# Triple_axis_digital_-_output_gyro_ITG-32.net
KiCad netlist of a schematic drawn in EAGLE
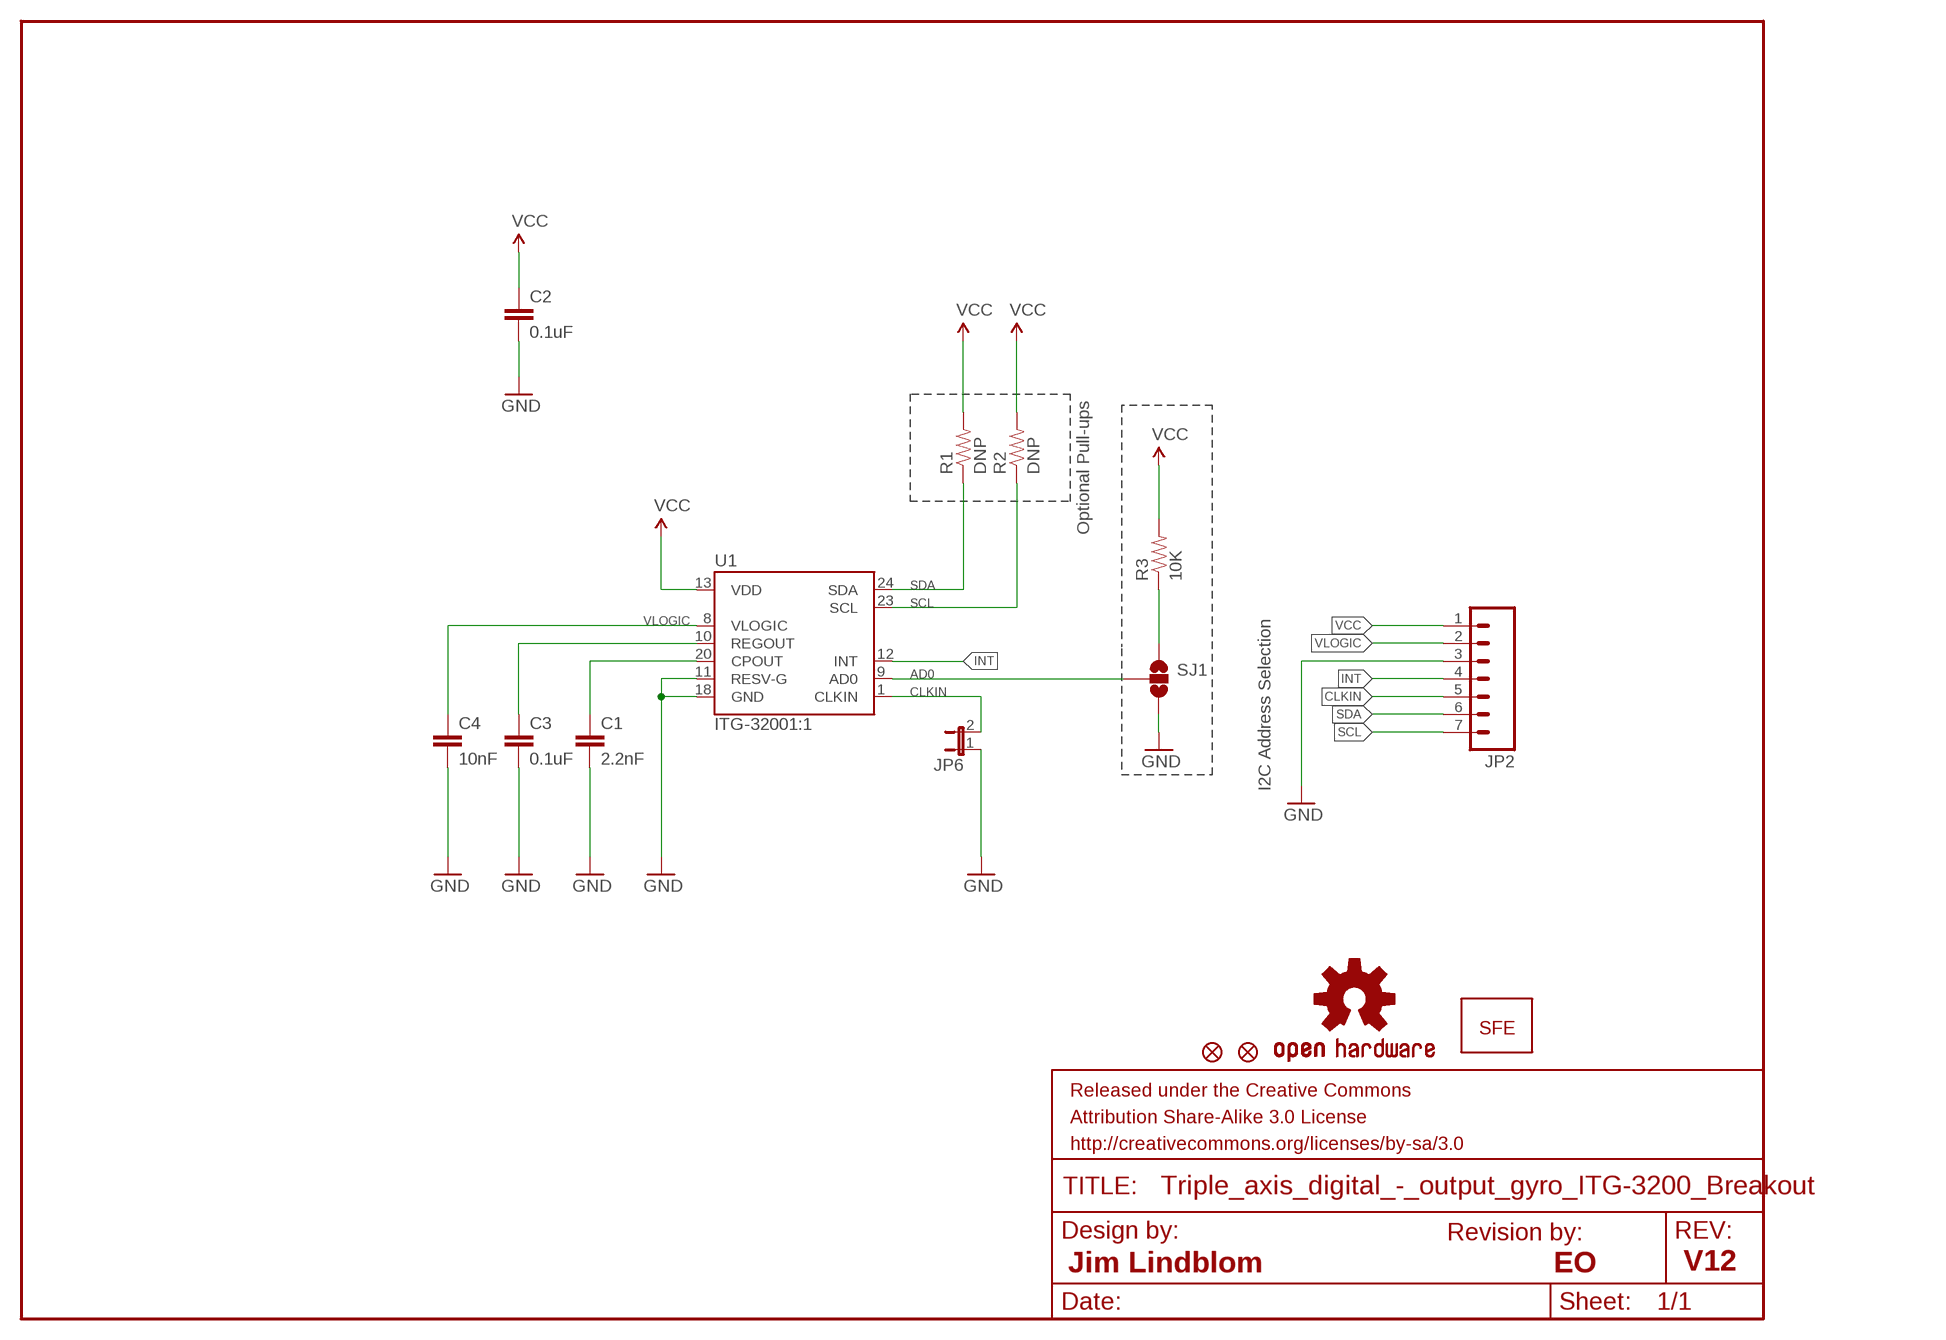
[diagram p0: schematic, sheet 1]

(export (version "E")
  (design (tool "Eeschema 10.0.6"))
  (components
    (comp (ref "C1")
      (value "2.2nF")
      (footprint "eagle-import:0603-CAP")
      (libsource (lib "eagle-import") (part "CAP0603-CAP"))
    )
    (comp (ref "C2")
      (value "0.1uF")
      (footprint "eagle-import:0603-CAP")
      (libsource (lib "eagle-import") (part "CAP0603-CAP"))
    )
    (comp (ref "C3")
      (value "0.1uF")
      (footprint "eagle-import:0603-CAP")
      (libsource (lib "eagle-import") (part "CAP0603-CAP"))
    )
    (comp (ref "C4")
      (value "10nF")
      (footprint "eagle-import:0603-CAP")
      (libsource (lib "eagle-import") (part "CAP0603-CAP"))
    )
    (comp (ref "FID1")
      (value "FIDUCIALUFIDUCIAL")
      (footprint "eagle-import:MICRO-FIDUCIAL")
      (libsource (lib "eagle-import") (part "FIDUCIALUFIDUCIAL"))
    )
    (comp (ref "FID2")
      (value "FIDUCIALUFIDUCIAL")
      (footprint "eagle-import:MICRO-FIDUCIAL")
      (libsource (lib "eagle-import") (part "FIDUCIALUFIDUCIAL"))
    )
    (comp (ref "FRAME1")
      (value "FRAME-LETTER")
      (footprint "eagle-import:CREATIVE_COMMONS")
      (libsource (lib "eagle-import") (part "FRAME-LETTER"))
    )
    (comp (ref "JP2")
      (value "M07")
      (footprint "eagle-import:1X07")
      (libsource (lib "eagle-import") (part "M07"))
    )
    (comp (ref "JP6")
      (value "JUMPER-2SMD-NO")
      (footprint "eagle-import:SJ_2S-NO")
      (libsource (lib "eagle-import") (part "JUMPER-2SMD-NO"))
    )
    (comp (ref "LOGO1")
      (value "OSHW-LOGOS")
      (footprint "eagle-import:OSHW-LOGO-S")
      (libsource (lib "eagle-import") (part "OSHW-LOGOS"))
    )
    (comp (ref "LOGO2")
      (value "LOGO-SFESK")
      (footprint "eagle-import:SFE-LOGO-FLAME")
      (libsource (lib "eagle-import") (part "LOGO-SFESK"))
    )
    (comp (ref "R1")
      (value "DNP")
      (footprint "eagle-import:0603-RES")
      (libsource (lib "eagle-import") (part "RESISTOR0603-RES"))
    )
    (comp (ref "R2")
      (value "DNP")
      (footprint "eagle-import:0603-RES")
      (libsource (lib "eagle-import") (part "RESISTOR0603-RES"))
    )
    (comp (ref "R3")
      (value "10K")
      (footprint "eagle-import:0603-RES")
      (libsource (lib "eagle-import") (part "10KOHM1/10W1%(0603)0603"))
    )
    (comp (ref "SJ1")
      (value "SOLDERJUMPER_2WAYPASTE1&2")
      (footprint "eagle-import:SJ_3_PASTE1&2")
      (libsource (lib "eagle-import") (part "SOLDERJUMPER_2WAYPASTE1&2"))
    )
    (comp (ref "U1")
      (value "ITG-32001:1")
      (footprint "eagle-import:QFN-24_ITG3200_1_1")
      (libsource (lib "eagle-import") (part "ITG-32001{colon}1"))
    )
  )
  (nets
    (net (code "1") (name "/AD0") (class "Default")
      (node (ref "SJ1") (pin "2") (pinfunction "2_2") (pintype "passive"))
      (node (ref "U1") (pin "9") (pinfunction "AD0_9") (pintype "bidirectional"))
    )
    (net (code "2") (name "CLKIN") (class "Default")
      (node (ref "JP2") (pin "5") (pinfunction "5_5") (pintype "passive"))
      (node (ref "JP6") (pin "2") (pinfunction "2_2") (pintype "passive"))
      (node (ref "U1") (pin "1") (pinfunction "CLKIN_1") (pintype "bidirectional"))
    )
    (net (code "3") (name "GND") (class "Default")
      (node (ref "C1") (pin "2") (pinfunction "2_2") (pintype "passive"))
      (node (ref "C2") (pin "2") (pinfunction "2_2") (pintype "passive"))
      (node (ref "C3") (pin "2") (pinfunction "2_2") (pintype "passive"))
      (node (ref "C4") (pin "2") (pinfunction "2_2") (pintype "passive"))
      (node (ref "JP2") (pin "3") (pinfunction "3_3") (pintype "passive"))
      (node (ref "JP6") (pin "1") (pinfunction "1_1") (pintype "passive"))
      (node (ref "SJ1") (pin "3") (pinfunction "3_3") (pintype "passive"))
      (node (ref "U1") (pin "11") (pinfunction "RESV-G_11") (pintype "bidirectional"))
      (node (ref "U1") (pin "18") (pinfunction "GND_18") (pintype "bidirectional"))
    )
    (net (code "4") (name "INT") (class "Default")
      (node (ref "JP2") (pin "4") (pinfunction "4_4") (pintype "passive"))
      (node (ref "U1") (pin "12") (pinfunction "INT_12") (pintype "bidirectional"))
    )
    (net (code "5") (name "Net-(R3-Pad1)") (class "Default")
      (node (ref "R3") (pin "1") (pinfunction "1_1") (pintype "passive"))
      (node (ref "SJ1") (pin "1") (pinfunction "1_1") (pintype "passive"))
    )
    (net (code "6") (name "Net-(U1-CPOUT)") (class "Default")
      (node (ref "C1") (pin "1") (pinfunction "1_1") (pintype "passive"))
      (node (ref "U1") (pin "20") (pinfunction "CPOUT_20") (pintype "bidirectional"))
    )
    (net (code "7") (name "Net-(U1-REGOUT)") (class "Default")
      (node (ref "C3") (pin "1") (pinfunction "1_1") (pintype "passive"))
      (node (ref "U1") (pin "10") (pinfunction "REGOUT_10") (pintype "bidirectional"))
    )
    (net (code "8") (name "SCL") (class "Default")
      (node (ref "JP2") (pin "7") (pinfunction "7_7") (pintype "passive"))
      (node (ref "R2") (pin "1") (pinfunction "1_1") (pintype "passive"))
      (node (ref "U1") (pin "23") (pinfunction "SCL_23") (pintype "bidirectional"))
    )
    (net (code "9") (name "SDA") (class "Default")
      (node (ref "JP2") (pin "6") (pinfunction "6_6") (pintype "passive"))
      (node (ref "R1") (pin "1") (pinfunction "1_1") (pintype "passive"))
      (node (ref "U1") (pin "24") (pinfunction "SDA_24") (pintype "bidirectional"))
    )
    (net (code "10") (name "VCC") (class "Default")
      (node (ref "C2") (pin "1") (pinfunction "1_1") (pintype "passive"))
      (node (ref "JP2") (pin "1") (pinfunction "1_1") (pintype "passive"))
      (node (ref "R1") (pin "2") (pinfunction "2_2") (pintype "passive"))
      (node (ref "R2") (pin "2") (pinfunction "2_2") (pintype "passive"))
      (node (ref "R3") (pin "2") (pinfunction "2_2") (pintype "passive"))
      (node (ref "U1") (pin "13") (pinfunction "VDD_13") (pintype "bidirectional"))
    )
    (net (code "11") (name "VLOGIC") (class "Default")
      (node (ref "C4") (pin "1") (pinfunction "1_1") (pintype "passive"))
      (node (ref "JP2") (pin "2") (pinfunction "2_2") (pintype "passive"))
      (node (ref "U1") (pin "8") (pinfunction "VLOGIC_8") (pintype "bidirectional"))
    )
  )
)
